# 485Driver_MAX3462.net
KiCad netlist of a schematic drawn in Altium Designer
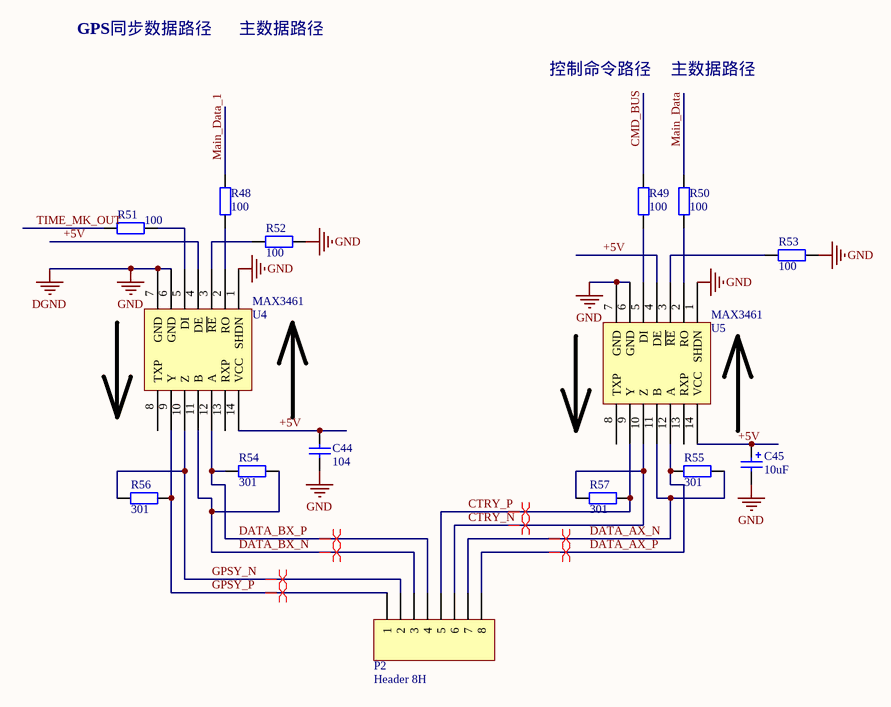
[diagram p0: 485Driver_MAX3462.SchDoc]

(export (version "E")
  (design (tool "Eeschema 10.0.6"))
  (components
    (comp (ref "C44")
      (value "104")
      (footprint "0805C")
      (description "Capacitor")
      (fields (field (name "PUBLISHER") "Altium Limited"))
      (libsource (lib "Miscellaneous Devices") (part "Cap"))
    )
    (comp (ref "C45")
      (value "10uF")
      (footprint "C68uF")
      (description "Polarized Capacitor (Axial)")
      (fields (field (name "PUBLISHER") "Altium Limited"))
      (libsource (lib "Miscellaneous Devices") (part "Cap Pol2"))
    )
    (comp (ref "P2")
      (value "Header 8H")
      (footprint "HDR1X8H")
      (description "Header, 8-Pin, Right Angle")
      (fields (field (name "PUBLISHER") "Altium Limited"))
      (libsource (lib "Miscellaneous Connectors") (part "Header 8H"))
    )
    (comp (ref "R48")
      (value "100")
      (footprint "0805R")
      (description "Resistor")
      (fields (field (name "PUBLISHER") "Altium Limited"))
      (libsource (lib "") (part "Res2_1"))
    )
    (comp (ref "R49")
      (value "100")
      (footprint "0805R")
      (description "Resistor")
      (fields (field (name "PUBLISHER") "Altium Limited"))
      (libsource (lib "") (part "Res2_1"))
    )
    (comp (ref "R50")
      (value "100")
      (footprint "0805R")
      (description "Resistor")
      (fields (field (name "PUBLISHER") "Altium Limited"))
      (libsource (lib "") (part "Res2_1"))
    )
    (comp (ref "R51")
      (value "100")
      (footprint "0805R")
      (description "Resistor")
      (fields (field (name "PUBLISHER") "Altium Limited"))
      (libsource (lib "Miscellaneous Devices") (part "Res2"))
    )
    (comp (ref "R52")
      (value "100")
      (footprint "0805R")
      (description "Resistor")
      (fields (field (name "PUBLISHER") "Altium Limited"))
      (libsource (lib "") (part "Res2_2"))
    )
    (comp (ref "R53")
      (value "100")
      (footprint "0805R")
      (description "Resistor")
      (fields (field (name "PUBLISHER") "Altium Limited"))
      (libsource (lib "") (part "Res2_2"))
    )
    (comp (ref "R54")
      (value "301")
      (footprint "0805R")
      (description "Resistor")
      (fields (field (name "PUBLISHER") "Altium Limited"))
      (libsource (lib "Miscellaneous Devices") (part "Res2"))
    )
    (comp (ref "R55")
      (value "301")
      (footprint "0805R")
      (description "Resistor")
      (fields (field (name "PUBLISHER") "Altium Limited"))
      (libsource (lib "Miscellaneous Devices") (part "Res2"))
    )
    (comp (ref "R56")
      (value "301")
      (footprint "0805R")
      (description "Resistor")
      (fields (field (name "PUBLISHER") "Altium Limited"))
      (libsource (lib "Miscellaneous Devices") (part "Res2"))
    )
    (comp (ref "R57")
      (value "301")
      (footprint "0805R")
      (description "Resistor")
      (fields (field (name "PUBLISHER") "Altium Limited"))
      (libsource (lib "Miscellaneous Devices") (part "Res2"))
    )
    (comp (ref "U4") (value "MAX3461") (footprint "SOP14") (libsource (lib "Schlib1") (part "MAX3461")))
    (comp (ref "U5") (value "MAX3461") (footprint "SOP14") (libsource (lib "Schlib1") (part "MAX3461")))
  )
  (nets
    (net (code "1") (name "/+5V") (class "Default")
      (node (ref "C44") (pin "2") (pinfunction "2_2") (pintype "passive"))
      (node (ref "C45") (pin "1") (pinfunction "1_1") (pintype "passive"))
      (node (ref "U4") (pin "14") (pinfunction "VCC_14") (pintype "passive"))
      (node (ref "U4") (pin "4") (pinfunction "DE_4") (pintype "passive"))
      (node (ref "U5") (pin "14") (pinfunction "VCC_14") (pintype "passive"))
      (node (ref "U5") (pin "4") (pinfunction "DE_4") (pintype "passive"))
    )
    (net (code "2") (name "/CMD_BUS") (class "Default")
      (node (ref "R49") (pin "1") (pinfunction "1_1") (pintype "passive"))
    )
    (net (code "3") (name "/CTRY_N") (class "Default")
      (node (ref "P2") (pin "6") (pinfunction "6_6") (pintype "passive"))
      (node (ref "R57") (pin "2") (pinfunction "2_2") (pintype "passive"))
      (node (ref "U5") (pin "10") (pinfunction "Z_10") (pintype "passive"))
    )
    (net (code "4") (name "/CTRY_P") (class "Default")
      (node (ref "P2") (pin "5") (pinfunction "5_5") (pintype "passive"))
      (node (ref "R57") (pin "1") (pinfunction "1_1") (pintype "passive"))
      (node (ref "U5") (pin "9") (pinfunction "Y_9") (pintype "passive"))
    )
    (net (code "5") (name "/DATA_AX_N") (class "Default")
      (node (ref "P2") (pin "7") (pinfunction "7_7") (pintype "passive"))
      (node (ref "R55") (pin "1") (pinfunction "1_1") (pintype "passive"))
      (node (ref "U5") (pin "11") (pinfunction "B_11") (pintype "passive"))
    )
    (net (code "6") (name "/DATA_AX_P") (class "Default")
      (node (ref "P2") (pin "8") (pinfunction "8_8") (pintype "passive"))
      (node (ref "R55") (pin "2") (pinfunction "2_2") (pintype "passive"))
      (node (ref "U5") (pin "12") (pinfunction "A_12") (pintype "passive"))
    )
    (net (code "7") (name "/DATA_BX_N") (class "Default")
      (node (ref "P2") (pin "3") (pinfunction "3_3") (pintype "passive"))
      (node (ref "R54") (pin "1") (pinfunction "1_1") (pintype "passive"))
      (node (ref "U4") (pin "11") (pinfunction "B_11") (pintype "passive"))
    )
    (net (code "8") (name "/DATA_BX_P") (class "Default")
      (node (ref "P2") (pin "4") (pinfunction "4_4") (pintype "passive"))
      (node (ref "R54") (pin "2") (pinfunction "2_2") (pintype "passive"))
      (node (ref "U4") (pin "12") (pinfunction "A_12") (pintype "passive"))
    )
    (net (code "9") (name "/GPSY_N") (class "Default")
      (node (ref "P2") (pin "2") (pinfunction "2_2") (pintype "passive"))
      (node (ref "R56") (pin "2") (pinfunction "2_2") (pintype "passive"))
      (node (ref "U4") (pin "10") (pinfunction "Z_10") (pintype "passive"))
    )
    (net (code "10") (name "/GPSY_P") (class "Default")
      (node (ref "P2") (pin "1") (pinfunction "1_1") (pintype "passive"))
      (node (ref "R56") (pin "1") (pinfunction "1_1") (pintype "passive"))
      (node (ref "U4") (pin "9") (pinfunction "Y_9") (pintype "passive"))
    )
    (net (code "11") (name "/Main_Data") (class "Default")
      (node (ref "R50") (pin "1") (pinfunction "1_1") (pintype "passive"))
    )
    (net (code "12") (name "/Main_Data_1") (class "Default")
      (node (ref "R48") (pin "1") (pinfunction "1_1") (pintype "passive"))
    )
    (net (code "13") (name "/TIME_MK_OUT") (class "Default")
      (node (ref "R51") (pin "2") (pinfunction "2_2") (pintype "passive"))
    )
    (net (code "14") (name "DGND") (class "Default")
      (node (ref "C44") (pin "1") (pinfunction "1_1") (pintype "passive"))
      (node (ref "C45") (pin "2") (pinfunction "2_2") (pintype "passive"))
      (node (ref "R52") (pin "2") (pinfunction "2_2") (pintype "passive"))
      (node (ref "R53") (pin "2") (pinfunction "2_2") (pintype "passive"))
      (node (ref "U4") (pin "1") (pinfunction "SHDN_1") (pintype "passive"))
      (node (ref "U4") (pin "6") (pinfunction "GND_6") (pintype "passive"))
      (node (ref "U4") (pin "7") (pinfunction "GND_7") (pintype "passive"))
      (node (ref "U5") (pin "1") (pinfunction "SHDN_1") (pintype "passive"))
      (node (ref "U5") (pin "6") (pinfunction "GND_6") (pintype "passive"))
      (node (ref "U5") (pin "7") (pinfunction "GND_7") (pintype "passive"))
    )
    (net (code "15") (name "Net-(U4-DI)") (class "Default")
      (node (ref "R51") (pin "1") (pinfunction "1_1") (pintype "passive"))
      (node (ref "U4") (pin "5") (pinfunction "DI_5") (pintype "passive"))
    )
    (net (code "16") (name "Net-(U4-RO)") (class "Default")
      (node (ref "R48") (pin "2") (pinfunction "2_2") (pintype "passive"))
      (node (ref "U4") (pin "2") (pinfunction "RO_2") (pintype "passive"))
    )
    (net (code "17") (name "Net-(U4-~{RE})") (class "Default")
      (node (ref "R52") (pin "1") (pinfunction "1_1") (pintype "passive"))
      (node (ref "U4") (pin "3") (pinfunction "~{RE}_3") (pintype "passive"))
    )
    (net (code "18") (name "Net-(U5-DI)") (class "Default")
      (node (ref "R49") (pin "2") (pinfunction "2_2") (pintype "passive"))
      (node (ref "U5") (pin "5") (pinfunction "DI_5") (pintype "passive"))
    )
    (net (code "19") (name "Net-(U5-RO)") (class "Default")
      (node (ref "R50") (pin "2") (pinfunction "2_2") (pintype "passive"))
      (node (ref "U5") (pin "2") (pinfunction "RO_2") (pintype "passive"))
    )
    (net (code "20") (name "Net-(U5-~{RE})") (class "Default")
      (node (ref "R53") (pin "1") (pinfunction "1_1") (pintype "passive"))
      (node (ref "U5") (pin "3") (pinfunction "~{RE}_3") (pintype "passive"))
    )
    (net (code "21") (name "unconnected-(U4-RXP-Pad13)") (class "Default")
      (node (ref "U4") (pin "13") (pinfunction "RXP_13") (pintype "passive"))
    )
    (net (code "22") (name "unconnected-(U4-TXP-Pad8)") (class "Default")
      (node (ref "U4") (pin "8") (pinfunction "TXP_8") (pintype "passive"))
    )
    (net (code "23") (name "unconnected-(U5-RXP-Pad13)") (class "Default")
      (node (ref "U5") (pin "13") (pinfunction "RXP_13") (pintype "passive"))
    )
    (net (code "24") (name "unconnected-(U5-TXP-Pad8)") (class "Default")
      (node (ref "U5") (pin "8") (pinfunction "TXP_8") (pintype "passive"))
    )
  )
)
